# adc.net
KiCad netlist of a schematic drawn in EAGLE
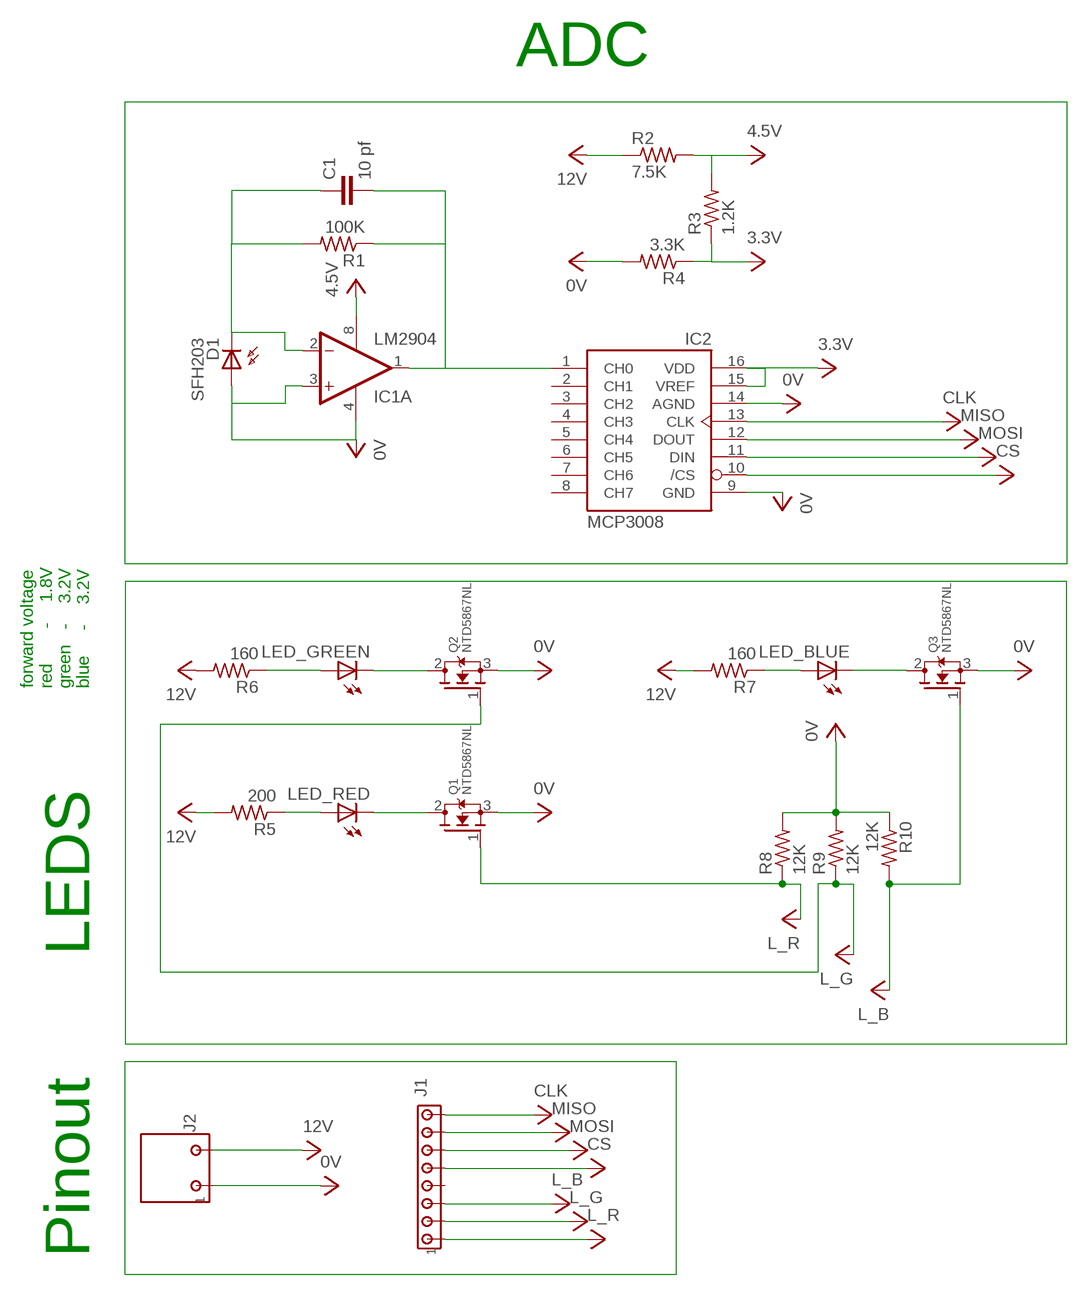
[diagram p0: schematic, sheet 1]

(export (version "E")
  (design (tool "Eeschema 10.0.6"))
  (components
    (comp (ref "C1")
      (value "10 pf")
      (footprint "eagle-import:C5B2.5")
      (libsource (lib "eagle-import") (part "C5/2.5"))
    )
    (comp (ref "D1")
      (value "SFH203")
      (footprint "eagle-import:SFH205")
      (libsource (lib "eagle-import") (part "SFH205"))
    )
    (comp (ref "IC1")
      (value "LM2904")
      (footprint "eagle-import:DIL08")
      (libsource (lib "eagle-import") (part "LM358N"))
    )
    (comp (ref "IC2")
      (value "MCP3008")
      (footprint "eagle-import:DIL16")
      (libsource (lib "eagle-import") (part "MCP3008"))
    )
    (comp (ref "J1")
      (value "MTA08-100")
      (footprint "eagle-import:10X08MTA")
      (libsource (lib "eagle-import") (part "MTA08-100"))
    )
    (comp (ref "J2")
      (value "MTA03-100")
      (footprint "eagle-import:10X03MTA")
      (libsource (lib "eagle-import") (part "MTA03-100"))
    )
    (comp (ref "LED_BLUE")
      (value "LED5MM")
      (footprint "eagle-import:LED5MM")
      (libsource (lib "eagle-import") (part "LED5MM"))
    )
    (comp (ref "LED_GREEN")
      (value "LED5MM")
      (footprint "eagle-import:LED5MM")
      (libsource (lib "eagle-import") (part "LED5MM"))
    )
    (comp (ref "LED_RED")
      (value "LED5MM")
      (footprint "eagle-import:LED5MM")
      (libsource (lib "eagle-import") (part "LED5MM"))
    )
    (comp (ref "Q1")
      (value "NTD5867NL")
      (footprint "eagle-import:TO220V")
      (libsource (lib "eagle-import") (part "MOSFET-NGDS_TO220V"))
    )
    (comp (ref "Q2")
      (value "NTD5867NL")
      (footprint "eagle-import:TO220V")
      (libsource (lib "eagle-import") (part "MOSFET-NGDS_TO220V"))
    )
    (comp (ref "Q3")
      (value "NTD5867NL")
      (footprint "eagle-import:TO220V")
      (libsource (lib "eagle-import") (part "MOSFET-NGDS_TO220V"))
    )
    (comp (ref "R1")
      (value "100K")
      (footprint "eagle-import:0207_10")
      (libsource (lib "eagle-import") (part "R-US_0207/10"))
    )
    (comp (ref "R2")
      (value "7.5K")
      (footprint "eagle-import:0207_10")
      (libsource (lib "eagle-import") (part "R-US_0207/10"))
    )
    (comp (ref "R3")
      (value "1.2K")
      (footprint "eagle-import:0207_10")
      (libsource (lib "eagle-import") (part "R-US_0207/10"))
    )
    (comp (ref "R4")
      (value "3.3K")
      (footprint "eagle-import:0207_10")
      (libsource (lib "eagle-import") (part "R-US_0207/10"))
    )
    (comp (ref "R5")
      (value "200")
      (footprint "eagle-import:0207_10")
      (libsource (lib "eagle-import") (part "R-US_0207/10"))
    )
    (comp (ref "R6")
      (value "160")
      (footprint "eagle-import:0207_10")
      (libsource (lib "eagle-import") (part "R-US_0207/10"))
    )
    (comp (ref "R7")
      (value "160")
      (footprint "eagle-import:0207_10")
      (libsource (lib "eagle-import") (part "R-US_0207/10"))
    )
    (comp (ref "R8")
      (value "12K")
      (footprint "eagle-import:0207_10")
      (libsource (lib "eagle-import") (part "R-US_0207/10"))
    )
    (comp (ref "R9")
      (value "12K")
      (footprint "eagle-import:0207_10")
      (libsource (lib "eagle-import") (part "R-US_0207/10"))
    )
    (comp (ref "R10")
      (value "12K")
      (footprint "eagle-import:0207_10")
      (libsource (lib "eagle-import") (part "R-US_0207/10"))
    )
  )
  (nets
    (net (code "1") (name "0V") (class "Default")
      (node (ref "D1") (pin "A") (pinfunction "A_A") (pintype "passive"))
      (node (ref "IC1") (pin "3") (pinfunction "+IN_3") (pintype "input"))
      (node (ref "IC1") (pin "4") (pinfunction "V-_4") (pintype "power_in"))
      (node (ref "IC2") (pin "14") (pinfunction "AGND_14") (pintype "power_in"))
      (node (ref "IC2") (pin "9") (pinfunction "GND_9") (pintype "power_in"))
      (node (ref "J2") (pin "1") (pinfunction "1_1") (pintype "passive"))
      (node (ref "Q1") (pin "3") (pinfunction "S_3") (pintype "bidirectional"))
      (node (ref "Q2") (pin "3") (pinfunction "S_3") (pintype "bidirectional"))
      (node (ref "Q3") (pin "3") (pinfunction "S_3") (pintype "bidirectional"))
      (node (ref "R10") (pin "1") (pinfunction "1_1") (pintype "passive"))
      (node (ref "R4") (pin "2") (pinfunction "2_2") (pintype "passive"))
      (node (ref "R8") (pin "2") (pinfunction "2_2") (pintype "passive"))
      (node (ref "R9") (pin "2") (pinfunction "2_2") (pintype "passive"))
    )
    (net (code "2") (name "3.3V") (class "Default")
      (node (ref "IC2") (pin "15") (pinfunction "VREF_15") (pintype "input"))
      (node (ref "IC2") (pin "16") (pinfunction "VDD_16") (pintype "power_in"))
      (node (ref "R3") (pin "1") (pinfunction "1_1") (pintype "passive"))
      (node (ref "R4") (pin "1") (pinfunction "1_1") (pintype "passive"))
    )
    (net (code "3") (name "4.5V") (class "Default")
      (node (ref "IC1") (pin "8") (pinfunction "V+_8") (pintype "power_in"))
      (node (ref "R2") (pin "2") (pinfunction "2_2") (pintype "passive"))
      (node (ref "R3") (pin "2") (pinfunction "2_2") (pintype "passive"))
    )
    (net (code "4") (name "12V") (class "Default")
      (node (ref "J2") (pin "3") (pinfunction "3_3") (pintype "passive"))
      (node (ref "R2") (pin "1") (pinfunction "1_1") (pintype "passive"))
      (node (ref "R5") (pin "2") (pinfunction "2_2") (pintype "passive"))
      (node (ref "R6") (pin "2") (pinfunction "2_2") (pintype "passive"))
      (node (ref "R7") (pin "2") (pinfunction "2_2") (pintype "passive"))
    )
    (net (code "5") (name "CLK") (class "Default")
      (node (ref "IC2") (pin "13") (pinfunction "CLK_13") (pintype "input"))
      (node (ref "J1") (pin "8") (pinfunction "8_8") (pintype "passive"))
    )
    (net (code "6") (name "CS") (class "Default")
      (node (ref "IC2") (pin "10") (pinfunction "/CS_10") (pintype "input"))
      (node (ref "J1") (pin "5") (pinfunction "5_5") (pintype "passive"))
    )
    (net (code "7") (name "L_B") (class "Default")
      (node (ref "J1") (pin "3") (pinfunction "3_3") (pintype "passive"))
      (node (ref "Q3") (pin "1") (pinfunction "G_1") (pintype "bidirectional"))
      (node (ref "R10") (pin "2") (pinfunction "2_2") (pintype "passive"))
    )
    (net (code "8") (name "L_G") (class "Default")
      (node (ref "J1") (pin "2") (pinfunction "2_2") (pintype "passive"))
      (node (ref "Q2") (pin "1") (pinfunction "G_1") (pintype "bidirectional"))
      (node (ref "R9") (pin "1") (pinfunction "1_1") (pintype "passive"))
    )
    (net (code "9") (name "L_R") (class "Default")
      (node (ref "J1") (pin "1") (pinfunction "1_1") (pintype "passive"))
      (node (ref "Q1") (pin "1") (pinfunction "G_1") (pintype "bidirectional"))
      (node (ref "R8") (pin "1") (pinfunction "1_1") (pintype "passive"))
    )
    (net (code "10") (name "MISO") (class "Default")
      (node (ref "IC2") (pin "12") (pinfunction "DOUT_12") (pintype "output"))
      (node (ref "J1") (pin "7") (pinfunction "7_7") (pintype "passive"))
    )
    (net (code "11") (name "MOSI") (class "Default")
      (node (ref "IC2") (pin "11") (pinfunction "DIN_11") (pintype "input"))
      (node (ref "J1") (pin "6") (pinfunction "6_6") (pintype "passive"))
    )
    (net (code "12") (name "Net-(D1-C)") (class "Default")
      (node (ref "C1") (pin "1") (pinfunction "1_1") (pintype "passive"))
      (node (ref "D1") (pin "K") (pinfunction "C_K") (pintype "passive"))
      (node (ref "IC1") (pin "2") (pinfunction "-IN_2") (pintype "input"))
      (node (ref "R1") (pin "2") (pinfunction "2_2") (pintype "passive"))
    )
    (net (code "13") (name "Net-(IC1A-OUT)") (class "Default")
      (node (ref "C1") (pin "2") (pinfunction "2_2") (pintype "passive"))
      (node (ref "IC1") (pin "1") (pinfunction "OUT_1") (pintype "output"))
      (node (ref "IC2") (pin "1") (pinfunction "CH0_1") (pintype "input"))
      (node (ref "R1") (pin "1") (pinfunction "1_1") (pintype "passive"))
    )
    (net (code "14") (name "Net-(LED_BLUE-C)") (class "Default")
      (node (ref "LED_BLUE") (pin "K") (pinfunction "C_K") (pintype "passive"))
      (node (ref "Q3") (pin "2") (pinfunction "D_2") (pintype "bidirectional"))
    )
    (net (code "15") (name "Net-(LED_BLUE-PadA)") (class "Default")
      (node (ref "LED_BLUE") (pin "A") (pinfunction "A_A") (pintype "passive"))
      (node (ref "R7") (pin "1") (pinfunction "1_1") (pintype "passive"))
    )
    (net (code "16") (name "Net-(LED_GREEN-C)") (class "Default")
      (node (ref "LED_GREEN") (pin "K") (pinfunction "C_K") (pintype "passive"))
      (node (ref "Q2") (pin "2") (pinfunction "D_2") (pintype "bidirectional"))
    )
    (net (code "17") (name "Net-(LED_GREEN-PadA)") (class "Default")
      (node (ref "LED_GREEN") (pin "A") (pinfunction "A_A") (pintype "passive"))
      (node (ref "R6") (pin "1") (pinfunction "1_1") (pintype "passive"))
    )
    (net (code "18") (name "Net-(LED_RED-C)") (class "Default")
      (node (ref "LED_RED") (pin "K") (pinfunction "C_K") (pintype "passive"))
      (node (ref "Q1") (pin "2") (pinfunction "D_2") (pintype "bidirectional"))
    )
    (net (code "19") (name "Net-(LED_RED-PadA)") (class "Default")
      (node (ref "LED_RED") (pin "A") (pinfunction "A_A") (pintype "passive"))
      (node (ref "R5") (pin "1") (pinfunction "1_1") (pintype "passive"))
    )
    (net (code "20") (name "unconnected-(IC2-CH1-Pad2)") (class "Default")
      (node (ref "IC2") (pin "2") (pinfunction "CH1_2") (pintype "input"))
    )
    (net (code "21") (name "unconnected-(IC2-CH2-Pad3)") (class "Default")
      (node (ref "IC2") (pin "3") (pinfunction "CH2_3") (pintype "input"))
    )
    (net (code "22") (name "unconnected-(IC2-CH3-Pad4)") (class "Default")
      (node (ref "IC2") (pin "4") (pinfunction "CH3_4") (pintype "input"))
    )
    (net (code "23") (name "unconnected-(IC2-CH4-Pad5)") (class "Default")
      (node (ref "IC2") (pin "5") (pinfunction "CH4_5") (pintype "input"))
    )
    (net (code "24") (name "unconnected-(IC2-CH5-Pad6)") (class "Default")
      (node (ref "IC2") (pin "6") (pinfunction "CH5_6") (pintype "input"))
    )
    (net (code "25") (name "unconnected-(IC2-CH6-Pad7)") (class "Default")
      (node (ref "IC2") (pin "7") (pinfunction "CH6_7") (pintype "input"))
    )
    (net (code "26") (name "unconnected-(IC2-CH7-Pad8)") (class "Default")
      (node (ref "IC2") (pin "8") (pinfunction "CH7_8") (pintype "input"))
    )
    (net (code "27") (name "unconnected-(J1-Pad4)") (class "Default")
      (node (ref "J1") (pin "4") (pinfunction "4_4") (pintype "passive"))
    )
  )
)
